# Agrobot_2_0.net
KiCad netlist of a schematic drawn in Altium Designer
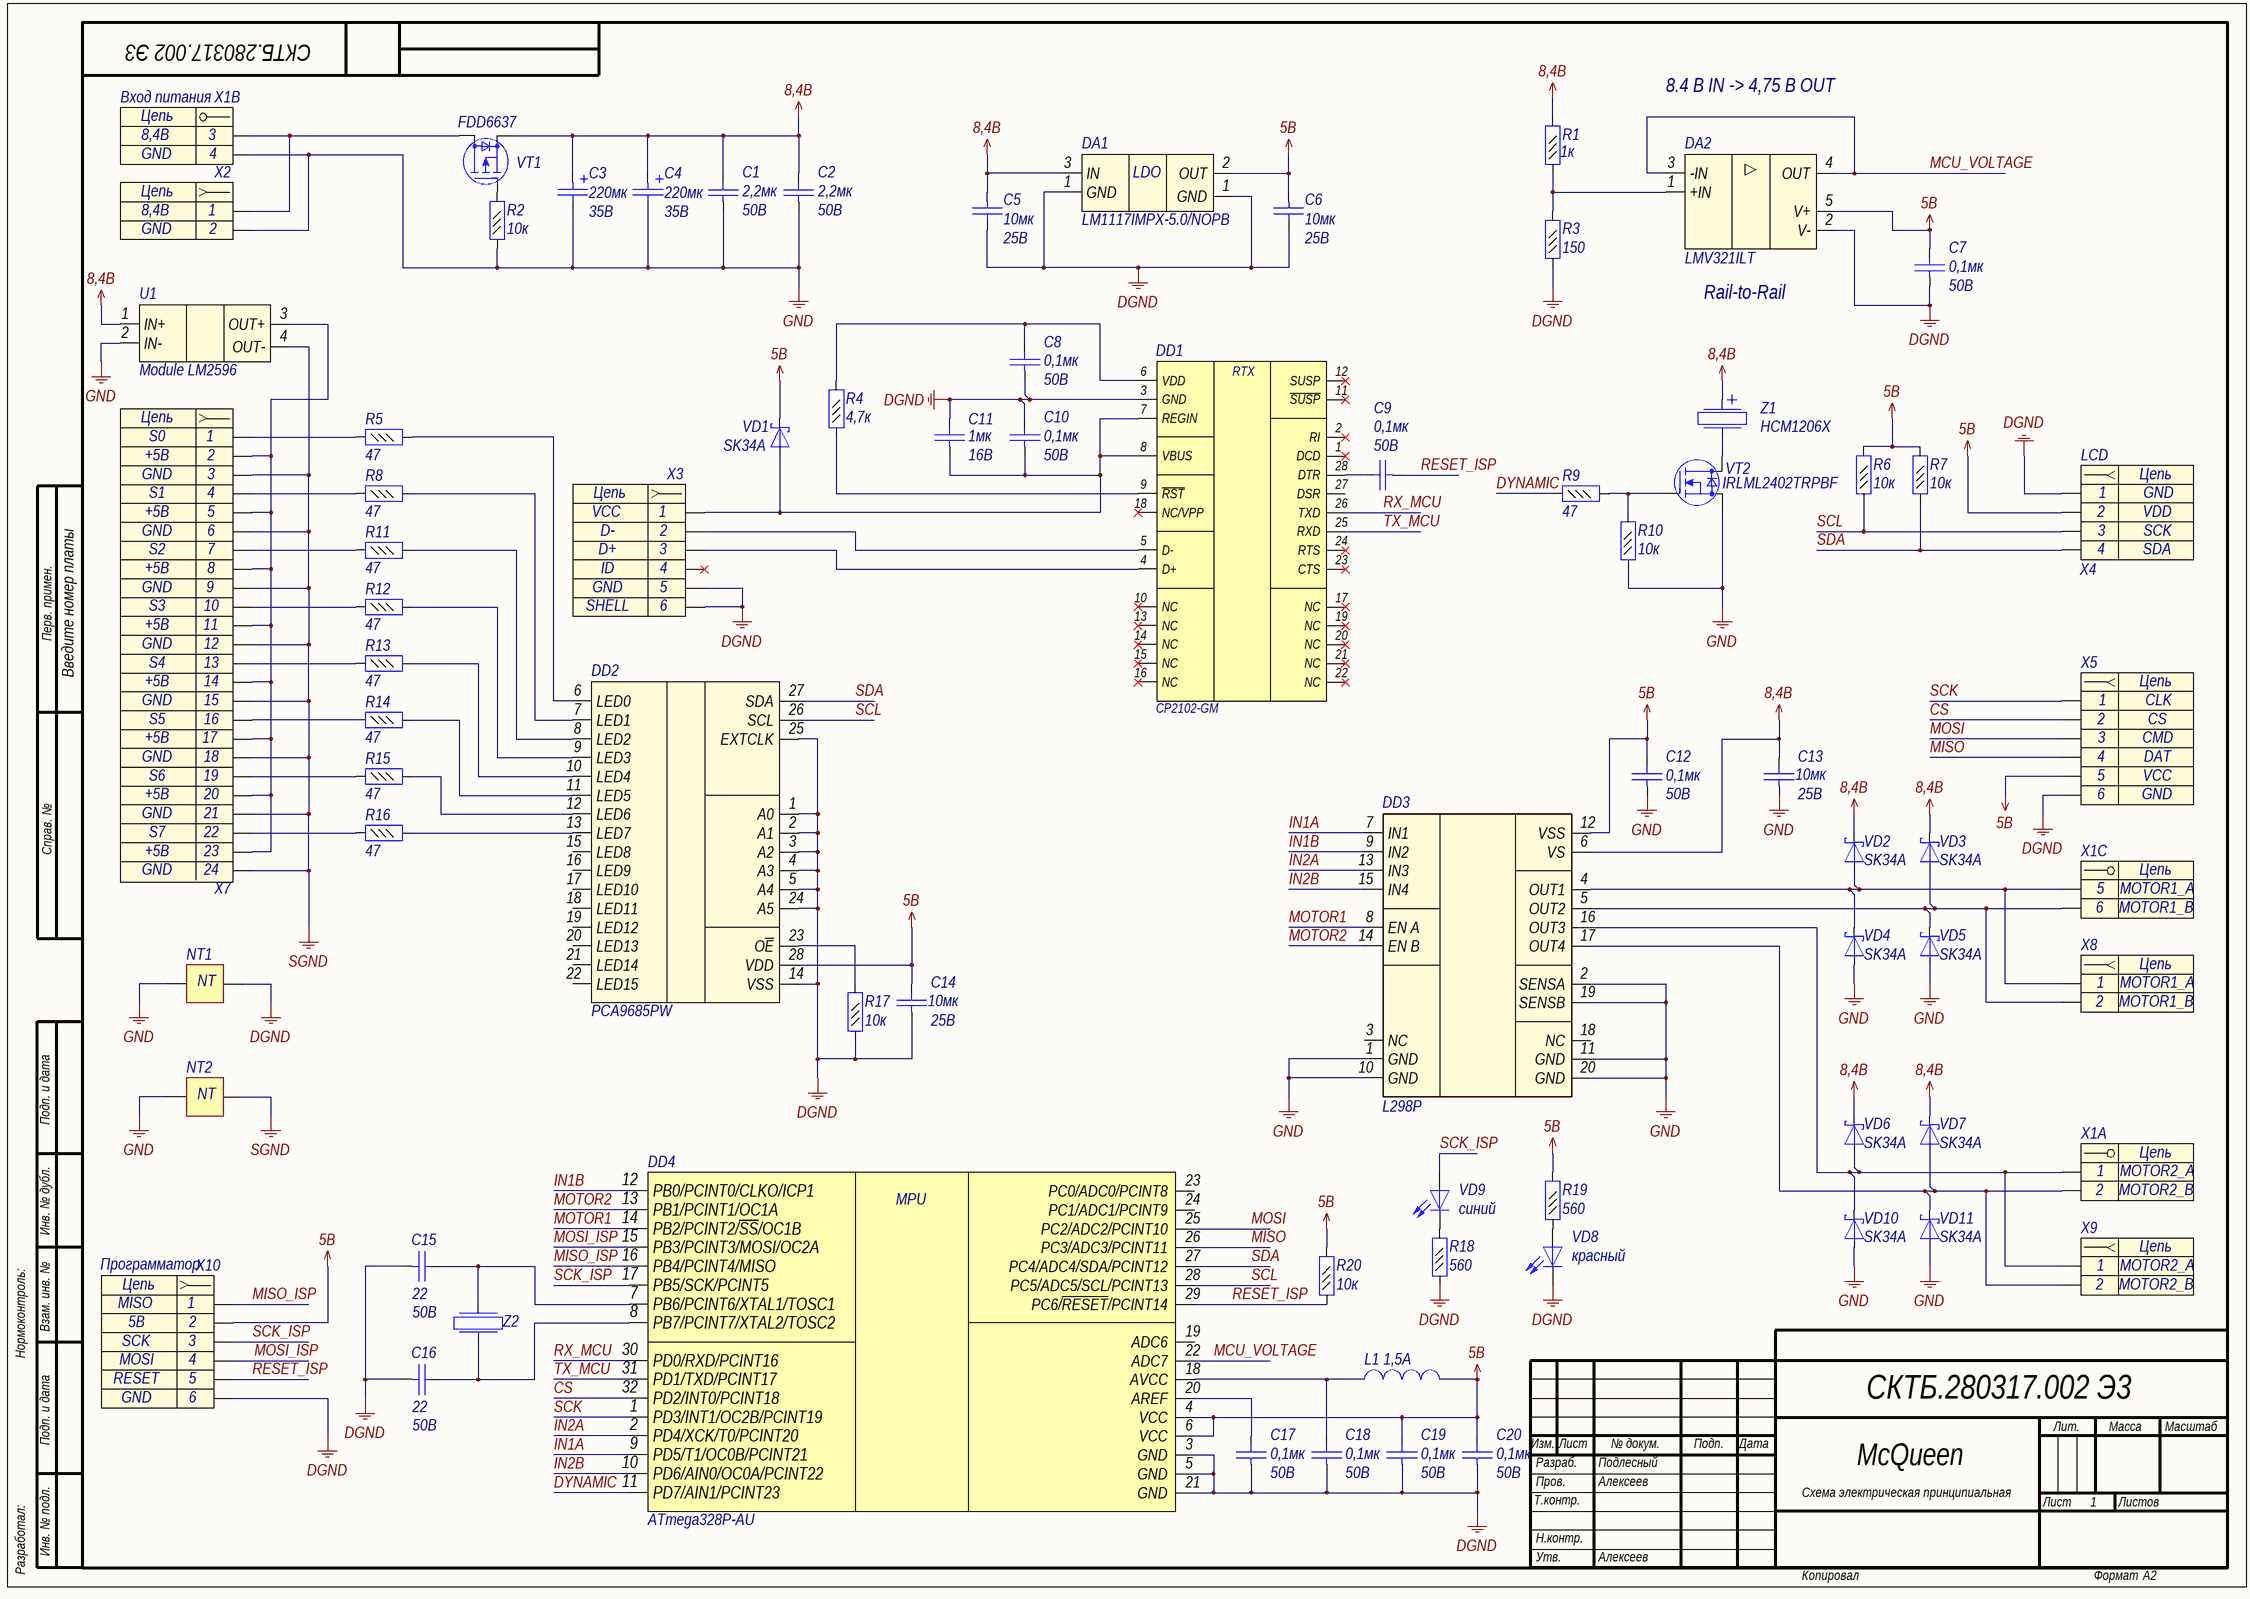
[diagram p0: Agrobot_2.0.SchDoc]

(export (version "E")
  (design (tool "Eeschema 10.0.6"))
  (components
    (comp (ref "C1")
      (value "2,2мк")
      (footprint "C1206")
      (description "Конденсатор")
      (fields
        (field (name "VOLTAGE") "50В")
        (field (name "PART NUMBER") "GRM31CR71H225KA88**L")
        (field (name "Comment") "Capacitor")
      )
      (libsource (lib "MOP44") (part "Capacitor"))
    )
    (comp (ref "C2")
      (value "2,2мк")
      (footprint "C1206")
      (description "Конденсатор")
      (fields
        (field (name "VOLTAGE") "50В")
        (field (name "PART NUMBER") "GRM31CR71H225KA88**L")
        (field (name "Comment") "Capacitor")
      )
      (libsource (lib "MOP44") (part "Capacitor"))
    )
    (comp (ref "C3")
      (value "220мк")
      (footprint "K50-35(8X11.5)_H")
      (description "Конденсатор полярный")
      (fields
        (field (name "VOLTAGE") "35В")
        (field (name "PART NUMBER") "TKR221M1VF11")
        (field (name "Comment") "Capacitor_pol")
      )
      (libsource (lib "MOP44") (part "Capacitor_pol"))
    )
    (comp (ref "C4")
      (value "220мк")
      (footprint "K50-35(8X11.5)_H_MIRROR")
      (description "Конденсатор полярный")
      (fields
        (field (name "VOLTAGE") "35В")
        (field (name "PART NUMBER") "TKR221M1VF11")
        (field (name "Comment") "Capacitor_pol")
      )
      (libsource (lib "MOP44") (part "Capacitor_pol"))
    )
    (comp (ref "C5")
      (value "10мк")
      (footprint "C1210")
      (description "Конденсатор")
      (fields (field (name "VOLTAGE") "25В") (field (name "PART NUMBER") "GRM32ER61A106K"))
      (libsource (lib "MOP44") (part "Capacitor"))
    )
    (comp (ref "C6")
      (value "10мк")
      (footprint "C1210")
      (description "Конденсатор")
      (fields (field (name "VOLTAGE") "25В") (field (name "PART NUMBER") "GRM32ER61A106K"))
      (libsource (lib "MOP44") (part "Capacitor"))
    )
    (comp (ref "C7")
      (value "0,1мк")
      (footprint "C0603")
      (description "Конденсатор")
      (fields (field (name "VOLTAGE") "50B") (field (name "PART NUMBER") "GRM188R71H104KA93D"))
      (libsource (lib "MOP44") (part "Capacitor"))
    )
    (comp (ref "C8")
      (value "0,1мк")
      (footprint "C0603")
      (description "Конденсатор")
      (fields (field (name "VOLTAGE") "50B") (field (name "PART NUMBER") "GRM188R71H104KA93D"))
      (libsource (lib "MOP44") (part "Capacitor"))
    )
    (comp (ref "C9")
      (value "0,1мк")
      (footprint "C0603")
      (description "Конденсатор")
      (fields (field (name "VOLTAGE") "50B") (field (name "PART NUMBER") "GRM188R71H104KA93D"))
      (libsource (lib "MOP44") (part "Capacitor"))
    )
    (comp (ref "C10")
      (value "0,1мк")
      (footprint "C0603")
      (description "Конденсатор")
      (fields (field (name "VOLTAGE") "50B") (field (name "PART NUMBER") "GRM188R71H104KA93D"))
      (libsource (lib "MOP44") (part "Capacitor"))
    )
    (comp (ref "C11")
      (value "1мк")
      (footprint "C0603")
      (description "Конденсатор")
      (fields (field (name "VOLTAGE") "16B") (field (name "PART NUMBER") "GRM188R71C105KA12D**"))
      (libsource (lib "MOP44") (part "Capacitor"))
    )
    (comp (ref "C12")
      (value "0,1мк")
      (footprint "C0603")
      (description "Конденсатор")
      (fields (field (name "VOLTAGE") "50B") (field (name "PART NUMBER") "GRM188R71H104KA93D"))
      (libsource (lib "MOP44") (part "Capacitor"))
    )
    (comp (ref "C13")
      (value "10мк")
      (footprint "C1210")
      (description "Конденсатор")
      (fields
        (field (name "VOLTAGE") "25В")
        (field (name "PART NUMBER") "GRM32ER61A106K")
        (field (name "Comment") "Capacitor")
      )
      (libsource (lib "MOP44") (part "Capacitor"))
    )
    (comp (ref "C14")
      (value "10мк")
      (footprint "C1210")
      (description "Конденсатор")
      (fields
        (field (name "VOLTAGE") "25В")
        (field (name "PART NUMBER") "GRM32ER61A106K")
        (field (name "Comment") "Capacitor")
      )
      (libsource (lib "MOP44") (part "Capacitor"))
    )
    (comp (ref "C15")
      (value "22")
      (footprint "C0603")
      (description "Конденсатор")
      (fields (field (name "VOLTAGE") "50B") (field (name "PART NUMBER") "CC0603JRNPO9BN220"))
      (libsource (lib "MOP44") (part "Capacitor"))
    )
    (comp (ref "C16")
      (value "22")
      (footprint "C0603")
      (description "Конденсатор")
      (fields (field (name "VOLTAGE") "50B") (field (name "PART NUMBER") "CC0603JRNPO9BN220"))
      (libsource (lib "MOP44") (part "Capacitor"))
    )
    (comp (ref "C17")
      (value "0,1мк")
      (footprint "C0603")
      (description "Конденсатор")
      (fields (field (name "VOLTAGE") "50B") (field (name "PART NUMBER") "GRM188R71H104KA93D"))
      (libsource (lib "MOP44") (part "Capacitor"))
    )
    (comp (ref "C18")
      (value "0,1мк")
      (footprint "C0603")
      (description "Конденсатор")
      (fields (field (name "VOLTAGE") "50B") (field (name "PART NUMBER") "GRM188R71H104KA93D"))
      (libsource (lib "MOP44") (part "Capacitor"))
    )
    (comp (ref "C19")
      (value "0,1мк")
      (footprint "C0603")
      (description "Конденсатор")
      (fields (field (name "VOLTAGE") "50B") (field (name "PART NUMBER") "GRM188R71H104KA93D"))
      (libsource (lib "MOP44") (part "Capacitor"))
    )
    (comp (ref "C20")
      (value "0,1мк")
      (footprint "C0603")
      (description "Конденсатор")
      (fields (field (name "VOLTAGE") "50B") (field (name "PART NUMBER") "GRM188R71H104KA93D"))
      (libsource (lib "MOP44") (part "Capacitor"))
    )
    (comp (ref "DA1")
      (value "LM1117IMPX")
      (footprint "SOT-223")
      (description "Low-Dropout Regulator for 5-V to 3.3-V Conversion")
      (fields
        (field (name "PART NUMBER") "LM1117IMPX-5.0/NOPB")
        (field (name "MANUFACTURER") "Texas Instruments")
      )
      (libsource (lib "MOP44") (part "LM1117IMPX"))
    )
    (comp (ref "DA2")
      (value "LMV321ILT")
      (footprint "SOT23-5")
      (description "HIGH-DRIVE OPERATIONAL AMPLIFIERS WITH SHUTDOWN")
      (libsource (lib "MOP44") (part "LMV321ILT"))
    )
    (comp (ref "DD1")
      (value "CP2102-GM")
      (footprint "QFN28")
      (description "USB-UART преобразователь")
      (libsource (lib "MOP44") (part "CP2102-GM"))
    )
    (comp (ref "DD2")
      (value "PCA9685PW")
      (footprint "TSSOP28")
      (description "Драйвер светодиода, 16 выходов")
      (libsource (lib "MOP44") (part "PCA9685PW"))
    )
    (comp (ref "DD3")
      (value "L298P")
      (footprint "POWERSO20")
      (description "FULL BRIDGE DC MOTOR DRIVER")
      (libsource (lib "MOP44") (part "L298P"))
    )
    (comp (ref "DD4")
      (value "ATmega328P-AU")
      (footprint "TQFP-32")
      (description "Микроконтроллер 8-Бит, picoPower, AVR, 20МГц, 32КБ Flash")
      (fields (field (name "PART NUMBER") "ATmega328P-AU"))
      (libsource (lib "MOP44") (part "ATmega328P-AU"))
    )
    (comp (ref "L1")
      (value "Inductor")
      (footprint "L0603")
      (description "EMI Suppression Filter")
      (fields (field (name "RATED CURRENT") "1,5A") (field (name "PART NUMBER") "BLM18PG181SN1D"))
      (libsource (lib "MOP44") (part "Inductor"))
    )
    (comp (ref "NT1")
      (value "Pofigistor")
      (footprint "Pofigistor0603")
      (libsource (lib "MOP44") (part "Pofigistor"))
    )
    (comp (ref "NT2")
      (value "Pofigistor")
      (footprint "Pofigistor0603")
      (libsource (lib "MOP44") (part "Pofigistor"))
    )
    (comp (ref "R1")
      (value "1к")
      (footprint "R0603")
      (description "Резистор")
      (fields (field (name "PART NUMBER") "RC0603FR-071KL") (field (name "POWER") "0,062Вт"))
      (libsource (lib "") (part "Resistor_0,062Вт_1"))
    )
    (comp (ref "R2")
      (value "10к")
      (footprint "R0603")
      (description "Резистор")
      (fields (field (name "PART NUMBER") "RC0603FR-0710KL") (field (name "POWER") "0,062Вт"))
      (libsource (lib "") (part "Resistor_0,062Вт_1"))
    )
    (comp (ref "R3")
      (value "150")
      (footprint "R0603")
      (description "Резистор")
      (fields (field (name "PART NUMBER") "RC0603FR-07150RL") (field (name "POWER") "0,062Вт"))
      (libsource (lib "") (part "Resistor_0,062Вт_1"))
    )
    (comp (ref "R4")
      (value "4,7к")
      (footprint "R0603")
      (description "Резистор")
      (fields (field (name "PART NUMBER") "RC0603FR-074K7") (field (name "POWER") "0,062Вт"))
      (libsource (lib "") (part "Resistor_0,062Вт_1"))
    )
    (comp (ref "R5")
      (value "47")
      (footprint "R0603")
      (description "Резистор")
      (fields (field (name "PART NUMBER") "RC0603FR-0747RL") (field (name "POWER") "0,062Вт"))
      (libsource (lib "MOP44") (part "Resistor_0,062Вт"))
    )
    (comp (ref "R6")
      (value "10к")
      (footprint "R0603")
      (description "Резистор")
      (fields (field (name "PART NUMBER") "RC0603FR-0710KL") (field (name "POWER") "0,062Вт"))
      (libsource (lib "") (part "Resistor_0,062Вт_1"))
    )
    (comp (ref "R7")
      (value "10к")
      (footprint "R0603")
      (description "Резистор")
      (fields (field (name "PART NUMBER") "RC0603FR-0710KL") (field (name "POWER") "0,062Вт"))
      (libsource (lib "") (part "Resistor_0,062Вт_1"))
    )
    (comp (ref "R8")
      (value "47")
      (footprint "R0603")
      (description "Резистор")
      (fields (field (name "PART NUMBER") "RC0603FR-0747RL") (field (name "POWER") "0,062Вт"))
      (libsource (lib "MOP44") (part "Resistor_0,062Вт"))
    )
    (comp (ref "R9")
      (value "47")
      (footprint "R0603")
      (description "Резистор")
      (fields (field (name "PART NUMBER") "RC0603FR-0747RL") (field (name "POWER") "0,062Вт"))
      (libsource (lib "MOP44") (part "Resistor_0,062Вт"))
    )
    (comp (ref "R10")
      (value "10к")
      (footprint "R0603")
      (description "Резистор")
      (fields (field (name "PART NUMBER") "RC0603FR-0710KL") (field (name "POWER") "0,062Вт"))
      (libsource (lib "") (part "Resistor_0,062Вт_1"))
    )
    (comp (ref "R11")
      (value "47")
      (footprint "R0603")
      (description "Резистор")
      (fields (field (name "PART NUMBER") "RC0603FR-0747RL") (field (name "POWER") "0,062Вт"))
      (libsource (lib "MOP44") (part "Resistor_0,062Вт"))
    )
    (comp (ref "R12")
      (value "47")
      (footprint "R0603")
      (description "Резистор")
      (fields (field (name "PART NUMBER") "RC0603FR-0747RL") (field (name "POWER") "0,062Вт"))
      (libsource (lib "MOP44") (part "Resistor_0,062Вт"))
    )
    (comp (ref "R13")
      (value "47")
      (footprint "R0603")
      (description "Резистор")
      (fields (field (name "PART NUMBER") "RC0603FR-0747RL") (field (name "POWER") "0,062Вт"))
      (libsource (lib "MOP44") (part "Resistor_0,062Вт"))
    )
    (comp (ref "R14")
      (value "47")
      (footprint "R0603")
      (description "Резистор")
      (fields (field (name "PART NUMBER") "RC0603FR-0747RL") (field (name "POWER") "0,062Вт"))
      (libsource (lib "MOP44") (part "Resistor_0,062Вт"))
    )
    (comp (ref "R15")
      (value "47")
      (footprint "R0603")
      (description "Резистор")
      (fields (field (name "PART NUMBER") "RC0603FR-0747RL") (field (name "POWER") "0,062Вт"))
      (libsource (lib "MOP44") (part "Resistor_0,062Вт"))
    )
    (comp (ref "R16")
      (value "47")
      (footprint "R0603")
      (description "Резистор")
      (fields (field (name "PART NUMBER") "RC0603FR-0747RL") (field (name "POWER") "0,062Вт"))
      (libsource (lib "MOP44") (part "Resistor_0,062Вт"))
    )
    (comp (ref "R17")
      (value "10к")
      (footprint "R0603")
      (description "Резистор")
      (fields (field (name "PART NUMBER") "RC0603FR-0710KL") (field (name "POWER") "0,062Вт"))
      (libsource (lib "") (part "Resistor_0,062Вт_1"))
    )
    (comp (ref "R18")
      (value "560")
      (footprint "R0603")
      (description "Резистор")
      (fields (field (name "PART NUMBER") "RC0603FR-07560RL") (field (name "POWER") "0,062Вт"))
      (libsource (lib "") (part "Resistor_0,062Вт_1"))
    )
    (comp (ref "R19")
      (value "560")
      (footprint "R0603")
      (description "Резистор")
      (fields (field (name "PART NUMBER") "RC0603FR-07560RL") (field (name "POWER") "0,062Вт"))
      (libsource (lib "") (part "Resistor_0,062Вт_1"))
    )
    (comp (ref "R20")
      (value "10к")
      (footprint "R0603")
      (description "Резистор")
      (fields (field (name "PART NUMBER") "RC0603FR-0710KL") (field (name "POWER") "0,062Вт"))
      (libsource (lib "") (part "Resistor_0,062Вт_1"))
    )
    (comp (ref "U1")
      (value "Module LM2596")
      (footprint "module LM2596")
      (description "Low-Dropout Regulator for 5-V to 3.3-V Conversion")
      (libsource (lib "MOP44") (part "Module LM2596"))
    )
    (comp (ref "VD1")
      (value "DiodeSchottky")
      (footprint "SMA")
      (description "Диод Шоттки")
      (fields (field (name "PART NUMBER") "SK34A"))
      (libsource (lib "MOP44") (part "DiodeSchottky"))
    )
    (comp (ref "VD2")
      (value "DiodeSchottky")
      (footprint "SMA")
      (description "Диод Шоттки")
      (fields (field (name "PART NUMBER") "SK34A"))
      (libsource (lib "MOP44") (part "DiodeSchottky"))
    )
    (comp (ref "VD3")
      (value "DiodeSchottky")
      (footprint "SMA")
      (description "Диод Шоттки")
      (fields (field (name "PART NUMBER") "SK34A"))
      (libsource (lib "MOP44") (part "DiodeSchottky"))
    )
    (comp (ref "VD4")
      (value "DiodeSchottky")
      (footprint "SMA")
      (description "Диод Шоттки")
      (fields (field (name "PART NUMBER") "SK34A"))
      (libsource (lib "MOP44") (part "DiodeSchottky"))
    )
    (comp (ref "VD5")
      (value "DiodeSchottky")
      (footprint "SMA")
      (description "Диод Шоттки")
      (fields (field (name "PART NUMBER") "SK34A"))
      (libsource (lib "MOP44") (part "DiodeSchottky"))
    )
    (comp (ref "VD6")
      (value "DiodeSchottky")
      (footprint "SMA")
      (description "Диод Шоттки")
      (fields (field (name "PART NUMBER") "SK34A"))
      (libsource (lib "MOP44") (part "DiodeSchottky"))
    )
    (comp (ref "VD7")
      (value "DiodeSchottky")
      (footprint "SMA")
      (description "Диод Шоттки")
      (fields (field (name "PART NUMBER") "SK34A"))
      (libsource (lib "MOP44") (part "DiodeSchottky"))
    )
    (comp (ref "VD8")
      (value "красный")
      (footprint "L_0805")
      (description "Светодиод")
      (fields (field (name "PART NUMBER") "KP-2012EC"))
      (libsource (lib "MOP44") (part "LED"))
    )
    (comp (ref "VD9")
      (value "синий")
      (footprint "L_0805")
      (description "Светодиод")
      (fields (field (name "PART NUMBER") "KP-2012MGC"))
      (libsource (lib "MOP44") (part "LED"))
    )
    (comp (ref "VD10")
      (value "DiodeSchottky")
      (footprint "SMA")
      (description "Диод Шоттки")
      (fields (field (name "PART NUMBER") "SK34A"))
      (libsource (lib "MOP44") (part "DiodeSchottky"))
    )
    (comp (ref "VD11")
      (value "DiodeSchottky")
      (footprint "SMA")
      (description "Диод Шоттки")
      (fields (field (name "PART NUMBER") "SK34A"))
      (libsource (lib "MOP44") (part "DiodeSchottky"))
    )
    (comp (ref "VT1")
      (value "P-MOSFET")
      (footprint "DPAK")
      (description "N-MOSFET")
      (fields (field (name "PART NUMBER") "FDD6637") (field (name "MANUFACTURER") "Fairchild Semiconductor"))
      (libsource (lib "MOP44") (part "P-MOSFET"))
    )
    (comp (ref "VT2")
      (value "N-MOSFET")
      (footprint "SOT23-3")
      (fields (field (name "PART NUMBER") "IRLML2402TRPBF"))
      (libsource (lib "MOP44") (part "N-MOSFET"))
    )
    (comp (ref "X1")
      (value "Вход питания")
      (footprint "TERMINAL-6WAY-5MM")
      (description "POWER")
      (libsource (lib "") (part "Header_6_motor_1"))
    )
    (comp (ref "X2")
      (value "Header_2_sct")
      (footprint "2HOLE_2.5")
      (description "Разъем - 2 конт. розетка")
      (libsource (lib "") (part "Header_2_sct_1"))
    )
    (comp (ref "X3")
      (value "Header_6_sct")
      (footprint "USB_MICRO_VERT")
      (description "Разъем - 6 конт. розетка")
      (fields (field (name "PART NUMBER") "MK5P"))
      (libsource (lib "") (part "Header_6_sct_1"))
    )
    (comp (ref "X4")
      (value "LCD")
      (footprint "PLS-4HOLES")
      (description "Разъем - 4 конт. розетка")
      (libsource (lib "MOP44") (part "Header_4_sct"))
    )
    (comp (ref "X5")
      (value "Header_6_sct")
      (footprint "PSP_ANTENNA")
      (description "Разъем - 6 конт. розетка")
      (libsource (lib "MOP44") (part "Header_6_sct"))
    )
    (comp (ref "X7")
      (value "Header_24_sct")
      (footprint "PLS-24-3")
      (description "Разъем - 5 конт. розетка")
      (libsource (lib "MOP44") (part "Header_24_sct"))
    )
    (comp (ref "X8")
      (value "Header_2_sct")
      (footprint "2HOLE_2.5")
      (description "Разъем - 2 конт. розетка")
      (libsource (lib "MOP44") (part "Header_2_sct"))
    )
    (comp (ref "X9")
      (value "Header_2_sct")
      (footprint "2HOLE_2.5")
      (description "Разъем - 2 конт. розетка")
      (libsource (lib "MOP44") (part "Header_2_sct"))
    )
    (comp (ref "X10")
      (value "Программатор")
      (footprint "PLS2-6")
      (description "Разъем - 6 конт. розетка")
      (libsource (lib "") (part "Header_6_sct_1"))
    )
    (comp (ref "Z1")
      (value "~")
      (footprint "Buzzer_gen_12mm")
      (description "Пьезоизлучатель звуковой без генератора")
      (fields (field (name "PART NUMBER") "HCM1206X"))
      (libsource (lib "MOP44") (part "Buzzer"))
    )
    (comp (ref "Z2")
      (value "Crystal")
      (footprint "HC-49SM")
      (description "Кварцевый резонатор")
      (fields (field (name "PART NUMBER") "16.000MHzHC-49SM"))
      (libsource (lib "MOP44") (part "Crystal"))
    )
  )
  (nets
    (net (code "1") (name "/CS") (class "Default")
      (node (ref "DD4") (pin "32") (pinfunction "PD2/INT0/PCINT18_32") (pintype "passive"))
      (node (ref "X5") (pin "2") (pinfunction "2_2") (pintype "passive"))
    )
    (net (code "2") (name "/DYNAMIC") (class "Default")
      (node (ref "DD4") (pin "11") (pinfunction "PD7/AIN1/PCINT23_11") (pintype "passive"))
      (node (ref "R9") (pin "1") (pinfunction "1_1") (pintype "passive"))
    )
    (net (code "3") (name "/IN1A") (class "Default")
      (node (ref "DD3") (pin "7") (pinfunction "IN1_7") (pintype "passive"))
      (node (ref "DD4") (pin "9") (pinfunction "PD5/T1/OC0B/PCINT21_9") (pintype "passive"))
    )
    (net (code "4") (name "/IN1B") (class "Default")
      (node (ref "DD3") (pin "9") (pinfunction "IN2_9") (pintype "passive"))
      (node (ref "DD4") (pin "12") (pinfunction "PB0/PCINT0/CLKO/ICP1_12") (pintype "passive"))
    )
    (net (code "5") (name "/IN2A") (class "Default")
      (node (ref "DD3") (pin "13") (pinfunction "IN3_13") (pintype "passive"))
      (node (ref "DD4") (pin "2") (pinfunction "PD4/XCK/T0/PCINT20_2") (pintype "passive"))
    )
    (net (code "6") (name "/IN2B") (class "Default")
      (node (ref "DD3") (pin "15") (pinfunction "IN4_15") (pintype "passive"))
      (node (ref "DD4") (pin "10") (pinfunction "PD6/AIN0/OC0A/PCINT22_10") (pintype "passive"))
    )
    (net (code "7") (name "/MCU_VOLTAGE") (class "Default")
      (node (ref "DA2") (pin "3") (pinfunction "-IN_3") (pintype "passive"))
      (node (ref "DA2") (pin "4") (pinfunction "OUT_4") (pintype "passive"))
      (node (ref "DD4") (pin "22") (pinfunction "ADC7_22") (pintype "passive"))
    )
    (net (code "8") (name "/MISO") (class "Default")
      (node (ref "DD4") (pin "26") (pinfunction "PC3/ADC3/PCINT11_26") (pintype "passive"))
      (node (ref "X5") (pin "4") (pinfunction "4_4") (pintype "passive"))
    )
    (net (code "9") (name "/MISO_ISP") (class "Default")
      (node (ref "DD4") (pin "16") (pinfunction "PB4/PCINT4/MISO_16") (pintype "passive"))
      (node (ref "X10") (pin "1") (pinfunction "1_1") (pintype "passive"))
    )
    (net (code "10") (name "/MOSI") (class "Default")
      (node (ref "DD4") (pin "25") (pinfunction "PC2/ADC2/PCINT10_25") (pintype "passive"))
      (node (ref "X5") (pin "3") (pinfunction "3_3") (pintype "passive"))
    )
    (net (code "11") (name "/MOSI_ISP") (class "Default")
      (node (ref "DD4") (pin "15") (pinfunction "PB3/PCINT3/MOSI/OC2A_15") (pintype "passive"))
      (node (ref "X10") (pin "4") (pinfunction "4_4") (pintype "passive"))
    )
    (net (code "12") (name "/MOTOR1") (class "Default")
      (node (ref "DD3") (pin "8") (pinfunction "EN_A_8") (pintype "passive"))
      (node (ref "DD4") (pin "14") (pinfunction "PB2/PCINT2/~{SS}/OC1B_14") (pintype "passive"))
    )
    (net (code "13") (name "/MOTOR2") (class "Default")
      (node (ref "DD3") (pin "14") (pinfunction "EN_B_14") (pintype "passive"))
      (node (ref "DD4") (pin "13") (pinfunction "PB1/PCINT1/OC1A_13") (pintype "passive"))
    )
    (net (code "14") (name "/RESET_ISP") (class "Default")
      (node (ref "C9") (pin "1") (pinfunction "1_1") (pintype "passive"))
      (node (ref "DD4") (pin "29") (pinfunction "PC6/~{RESET}/PCINT14_29") (pintype "passive"))
      (node (ref "R20") (pin "1") (pinfunction "1_1") (pintype "passive"))
      (node (ref "X10") (pin "5") (pinfunction "5_5") (pintype "passive"))
    )
    (net (code "15") (name "/RX_MCU") (class "Default")
      (node (ref "DD1") (pin "26") (pinfunction "TXD_26") (pintype "passive"))
      (node (ref "DD4") (pin "30") (pinfunction "PD0/RXD/PCINT16_30") (pintype "passive"))
    )
    (net (code "16") (name "/SCK") (class "Default")
      (node (ref "DD4") (pin "1") (pinfunction "PD3/INT1/OC2B/PCINT19_1") (pintype "passive"))
      (node (ref "X5") (pin "1") (pinfunction "1_1") (pintype "passive"))
    )
    (net (code "17") (name "/SCK_ISP") (class "Default")
      (node (ref "DD4") (pin "17") (pinfunction "PB5/SCK/PCINT5_17") (pintype "passive"))
      (node (ref "VD9") (pin "2") (pinfunction "A_2") (pintype "passive"))
      (node (ref "X10") (pin "3") (pinfunction "3_3") (pintype "passive"))
    )
    (net (code "18") (name "/SCL") (class "Default")
      (node (ref "DD2") (pin "26") (pinfunction "SCL_26") (pintype "power_in"))
      (node (ref "DD4") (pin "28") (pinfunction "PC5/ADC5/SCL/PCINT13_28") (pintype "passive"))
      (node (ref "R6") (pin "1") (pinfunction "1_1") (pintype "passive"))
      (node (ref "X4") (pin "3") (pinfunction "3_3") (pintype "passive"))
    )
    (net (code "19") (name "/SDA") (class "Default")
      (node (ref "DD2") (pin "27") (pinfunction "SDA_27") (pintype "power_in"))
      (node (ref "DD4") (pin "27") (pinfunction "PC4/ADC4/SDA/PCINT12_27") (pintype "passive"))
      (node (ref "R7") (pin "1") (pinfunction "1_1") (pintype "passive"))
      (node (ref "X4") (pin "4") (pinfunction "4_4") (pintype "passive"))
    )
    (net (code "20") (name "/TX_MCU") (class "Default")
      (node (ref "DD1") (pin "25") (pinfunction "RXD_25") (pintype "passive"))
      (node (ref "DD4") (pin "31") (pinfunction "PD1/TXD/PCINT17_31") (pintype "passive"))
    )
    (net (code "21") (name "5В") (class "Default")
      (node (ref "C12") (pin "2") (pinfunction "2_2") (pintype "passive"))
      (node (ref "C14") (pin "2") (pinfunction "2_2") (pintype "passive"))
      (node (ref "C19") (pin "2") (pinfunction "2_2") (pintype "passive"))
      (node (ref "C20") (pin "2") (pinfunction "2_2") (pintype "passive"))
      (node (ref "C6") (pin "1") (pinfunction "1_1") (pintype "passive"))
      (node (ref "C7") (pin "2") (pinfunction "2_2") (pintype "passive"))
      (node (ref "DA1") (pin "2") (pinfunction "OUT_2") (pintype "power_in"))
      (node (ref "DA2") (pin "5") (pinfunction "V+_5") (pintype "passive"))
      (node (ref "DD2") (pin "28") (pinfunction "VDD_28") (pintype "power_in"))
      (node (ref "DD3") (pin "12") (pinfunction "VSS_12") (pintype "passive"))
      (node (ref "DD4") (pin "4") (pinfunction "VCC_4") (pintype "passive"))
      (node (ref "DD4") (pin "6") (pinfunction "VCC_6") (pintype "passive"))
      (node (ref "L1") (pin "2") (pinfunction "2_2") (pintype "passive"))
      (node (ref "R19") (pin "2") (pinfunction "2_2") (pintype "passive"))
      (node (ref "R20") (pin "2") (pinfunction "2_2") (pintype "passive"))
      (node (ref "R6") (pin "2") (pinfunction "2_2") (pintype "passive"))
      (node (ref "R7") (pin "2") (pinfunction "2_2") (pintype "passive"))
      (node (ref "VD1") (pin "1") (pinfunction "K_1") (pintype "passive"))
      (node (ref "X10") (pin "2") (pinfunction "2_2") (pintype "passive"))
      (node (ref "X4") (pin "2") (pinfunction "2_2") (pintype "passive"))
      (node (ref "X5") (pin "5") (pinfunction "5_5") (pintype "passive"))
    )
    (net (code "22") (name "8,4В") (class "Default")
      (node (ref "C1") (pin "2") (pinfunction "2_2") (pintype "passive"))
      (node (ref "C13") (pin "2") (pinfunction "2_2") (pintype "passive"))
      (node (ref "C2") (pin "2") (pinfunction "2_2") (pintype "passive"))
      (node (ref "C3") (pin "1") (pinfunction "1_1") (pintype "passive"))
      (node (ref "C4") (pin "1") (pinfunction "1_1") (pintype "passive"))
      (node (ref "C5") (pin "1") (pinfunction "1_1") (pintype "passive"))
      (node (ref "DA1") (pin "3") (pinfunction "IN_3") (pintype "power_in"))
      (node (ref "DD3") (pin "6") (pinfunction "VS_6") (pintype "passive"))
      (node (ref "R1") (pin "2") (pinfunction "2_2") (pintype "passive"))
      (node (ref "U1") (pin "1") (pinfunction "IN+_1") (pintype "power_in"))
      (node (ref "VD2") (pin "1") (pinfunction "K_1") (pintype "passive"))
      (node (ref "VD3") (pin "1") (pinfunction "K_1") (pintype "passive"))
      (node (ref "VD6") (pin "1") (pinfunction "K_1") (pintype "passive"))
      (node (ref "VD7") (pin "1") (pinfunction "K_1") (pintype "passive"))
      (node (ref "VT1") (pin "3") (pinfunction "S_3") (pintype "passive"))
      (node (ref "Z1") (pin "1") (pinfunction "1_1") (pintype "passive"))
    )
    (net (code "23") (name "DGND") (class "Default")
      (node (ref "C10") (pin "2") (pinfunction "2_2") (pintype "passive"))
      (node (ref "C11") (pin "2") (pinfunction "2_2") (pintype "passive"))
      (node (ref "C14") (pin "1") (pinfunction "1_1") (pintype "passive"))
      (node (ref "C15") (pin "1") (pinfunction "1_1") (pintype "passive"))
      (node (ref "C16") (pin "1") (pinfunction "1_1") (pintype "passive"))
      (node (ref "C17") (pin "1") (pinfunction "1_1") (pintype "passive"))
      (node (ref "C18") (pin "1") (pinfunction "1_1") (pintype "passive"))
      (node (ref "C19") (pin "1") (pinfunction "1_1") (pintype "passive"))
      (node (ref "C20") (pin "1") (pinfunction "1_1") (pintype "passive"))
      (node (ref "C5") (pin "2") (pinfunction "2_2") (pintype "passive"))
      (node (ref "C6") (pin "2") (pinfunction "2_2") (pintype "passive"))
      (node (ref "C7") (pin "1") (pinfunction "1_1") (pintype "passive"))
      (node (ref "C8") (pin "1") (pinfunction "1_1") (pintype "passive"))
      (node (ref "DA1") (pin "1") (pinfunction "GND_1") (pintype "power_in"))
      (node (ref "DA2") (pin "2") (pinfunction "V-_2") (pintype "passive"))
      (node (ref "DD1") (pin "3") (pinfunction "GND_3") (pintype "passive"))
      (node (ref "DD2") (pin "1") (pinfunction "A0_1") (pintype "power_in"))
      (node (ref "DD2") (pin "14") (pinfunction "VSS_14") (pintype "power_in"))
      (node (ref "DD2") (pin "2") (pinfunction "A1_2") (pintype "power_in"))
      (node (ref "DD2") (pin "24") (pinfunction "A5_24") (pintype "power_in"))
      (node (ref "DD2") (pin "25") (pinfunction "EXTCLK_25") (pintype "power_in"))
      (node (ref "DD2") (pin "3") (pinfunction "A2_3") (pintype "power_in"))
      (node (ref "DD2") (pin "4") (pinfunction "A3_4") (pintype "power_in"))
      (node (ref "DD2") (pin "5") (pinfunction "A4_5") (pintype "power_in"))
      (node (ref "DD4") (pin "21") (pinfunction "GND_21") (pintype "passive"))
      (node (ref "DD4") (pin "3") (pinfunction "GND_3") (pintype "passive"))
      (node (ref "DD4") (pin "5") (pinfunction "GND_5") (pintype "passive"))
      (node (ref "NT1") (pin "2") (pinfunction "2_2") (pintype "passive"))
      (node (ref "R17") (pin "1") (pinfunction "1_1") (pintype "passive"))
      (node (ref "R18") (pin "1") (pinfunction "1_1") (pintype "passive"))
      (node (ref "R3") (pin "1") (pinfunction "1_1") (pintype "passive"))
      (node (ref "VD8") (pin "1") (pinfunction "K_1") (pintype "passive"))
      (node (ref "X10") (pin "6") (pinfunction "6_6") (pintype "passive"))
      (node (ref "X3") (pin "5") (pinfunction "5_5") (pintype "passive"))
      (node (ref "X3") (pin "6") (pinfunction "6_6") (pintype "passive"))
      (node (ref "X4") (pin "1") (pinfunction "1_1") (pintype "passive"))
      (node (ref "X5") (pin "6") (pinfunction "6_6") (pintype "passive"))
    )
    (net (code "24") (name "GND") (class "Default")
      (node (ref "C1") (pin "1") (pinfunction "1_1") (pintype "passive"))
      (node (ref "C12") (pin "1") (pinfunction "1_1") (pintype "passive"))
      (node (ref "C13") (pin "1") (pinfunction "1_1") (pintype "passive"))
      (node (ref "C2") (pin "1") (pinfunction "1_1") (pintype "passive"))
      (node (ref "C3") (pin "2") (pinfunction "2_2") (pintype "passive"))
      (node (ref "C4") (pin "2") (pinfunction "2_2") (pintype "passive"))
      (node (ref "DD3") (pin "1") (pinfunction "GND_1") (pintype "passive"))
      (node (ref "DD3") (pin "10") (pinfunction "GND_10") (pintype "passive"))
      (node (ref "DD3") (pin "11") (pinfunction "GND_11") (pintype "passive"))
      (node (ref "DD3") (pin "19") (pinfunction "SENSB_19") (pintype "passive"))
      (node (ref "DD3") (pin "2") (pinfunction "SENSA_2") (pintype "passive"))
      (node (ref "DD3") (pin "20") (pinfunction "GND_20") (pintype "passive"))
      (node (ref "NT1") (pin "1") (pinfunction "1_1") (pintype "passive"))
      (node (ref "NT2") (pin "1") (pinfunction "1_1") (pintype "passive"))
      (node (ref "R10") (pin "1") (pinfunction "1_1") (pintype "passive"))
      (node (ref "R2") (pin "1") (pinfunction "1_1") (pintype "passive"))
      (node (ref "U1") (pin "2") (pinfunction "IN-_2") (pintype "power_in"))
      (node (ref "VD10") (pin "2") (pinfunction "A_2") (pintype "passive"))
      (node (ref "VD11") (pin "2") (pinfunction "A_2") (pintype "passive"))
      (node (ref "VD4") (pin "2") (pinfunction "A_2") (pintype "passive"))
      (node (ref "VD5") (pin "2") (pinfunction "A_2") (pintype "passive"))
      (node (ref "VT2") (pin "2") (pinfunction "S_2") (pintype "passive"))
      (node (ref "X1") (pin "4") (pinfunction "4_4") (pintype "passive"))
      (node (ref "X2") (pin "2") (pinfunction "2_2") (pintype "passive"))
    )
    (net (code "25") (name "Net-(DA2-+IN)") (class "Default")
      (node (ref "DA2") (pin "1") (pinfunction "+IN_1") (pintype "passive"))
      (node (ref "R1") (pin "1") (pinfunction "1_1") (pintype "passive"))
      (node (ref "R3") (pin "2") (pinfunction "2_2") (pintype "passive"))
    )
    (net (code "26") (name "Net-(DD1-D+)") (class "Default")
      (node (ref "DD1") (pin "4") (pinfunction "D+_4") (pintype "passive"))
      (node (ref "X3") (pin "3") (pinfunction "3_3") (pintype "passive"))
    )
    (net (code "27") (name "Net-(DD1-D-)") (class "Default")
      (node (ref "DD1") (pin "5") (pinfunction "D-_5") (pintype "passive"))
      (node (ref "X3") (pin "2") (pinfunction "2_2") (pintype "passive"))
    )
    (net (code "28") (name "Net-(DD1-DTR)") (class "Default")
      (node (ref "C9") (pin "2") (pinfunction "2_2") (pintype "passive"))
      (node (ref "DD1") (pin "28") (pinfunction "DTR_28") (pintype "passive"))
    )
    (net (code "29") (name "Net-(DD1-REGIN)") (class "Default")
      (node (ref "C10") (pin "1") (pinfunction "1_1") (pintype "passive"))
      (node (ref "C11") (pin "1") (pinfunction "1_1") (pintype "passive"))
      (node (ref "DD1") (pin "7") (pinfunction "REGIN_7") (pintype "passive"))
      (node (ref "DD1") (pin "8") (pinfunction "VBUS_8") (pintype "passive"))
      (node (ref "VD1") (pin "2") (pinfunction "A_2") (pintype "passive"))
      (node (ref "X3") (pin "1") (pinfunction "1_1") (pintype "passive"))
    )
    (net (code "30") (name "Net-(DD1-VDD)") (class "Default")
      (node (ref "C8") (pin "2") (pinfunction "2_2") (pintype "passive"))
      (node (ref "DD1") (pin "6") (pinfunction "VDD_6") (pintype "passive"))
      (node (ref "R4") (pin "2") (pinfunction "2_2") (pintype "passive"))
    )
    (net (code "31") (name "Net-(DD1-~{RST})") (class "Default")
      (node (ref "DD1") (pin "9") (pinfunction "~{RST}_9") (pintype "passive"))
      (node (ref "R4") (pin "1") (pinfunction "1_1") (pintype "passive"))
    )
    (net (code "32") (name "Net-(DD2-LED0)") (class "Default")
      (node (ref "DD2") (pin "6") (pinfunction "LED0_6") (pintype "power_in"))
      (node (ref "R5") (pin "2") (pinfunction "2_2") (pintype "passive"))
    )
    (net (code "33") (name "Net-(DD2-LED1)") (class "Default")
      (node (ref "DD2") (pin "7") (pinfunction "LED1_7") (pintype "power_in"))
      (node (ref "R8") (pin "2") (pinfunction "2_2") (pintype "passive"))
    )
    (net (code "34") (name "Net-(DD2-LED2)") (class "Default")
      (node (ref "DD2") (pin "8") (pinfunction "LED2_8") (pintype "power_in"))
      (node (ref "R11") (pin "2") (pinfunction "2_2") (pintype "passive"))
    )
    (net (code "35") (name "Net-(DD2-LED3)") (class "Default")
      (node (ref "DD2") (pin "9") (pinfunction "LED3_9") (pintype "power_in"))
      (node (ref "R12") (pin "2") (pinfunction "2_2") (pintype "passive"))
    )
    (net (code "36") (name "Net-(DD2-LED4)") (class "Default")
      (node (ref "DD2") (pin "10") (pinfunction "LED4_10") (pintype "power_in"))
      (node (ref "R13") (pin "2") (pinfunction "2_2") (pintype "passive"))
    )
    (net (code "37") (name "Net-(DD2-LED5)") (class "Default")
      (node (ref "DD2") (pin "11") (pinfunction "LED5_11") (pintype "power_in"))
      (node (ref "R14") (pin "2") (pinfunction "2_2") (pintype "passive"))
    )
    (net (code "38") (name "Net-(DD2-LED6)") (class "Default")
      (node (ref "DD2") (pin "12") (pinfunction "LED6_12") (pintype "power_in"))
      (node (ref "R15") (pin "2") (pinfunction "2_2") (pintype "passive"))
    )
    (net (code "39") (name "Net-(DD2-LED7)") (class "Default")
      (node (ref "DD2") (pin "13") (pinfunction "LED7_13") (pintype "power_in"))
      (node (ref "R16") (pin "2") (pinfunction "2_2") (pintype "passive"))
    )
    (net (code "40") (name "Net-(DD2-O~{E})") (class "Default")
      (node (ref "DD2") (pin "23") (pinfunction "O~{E}_23") (pintype "power_in"))
      (node (ref "R17") (pin "2") (pinfunction "2_2") (pintype "passive"))
    )
    (net (code "41") (name "Net-(DD3-OUT1)") (class "Default")
      (node (ref "DD3") (pin "4") (pinfunction "OUT1_4") (pintype "passive"))
      (node (ref "VD2") (pin "2") (pinfunction "A_2") (pintype "passive"))
      (node (ref "VD4") (pin "1") (pinfunction "K_1") (pintype "passive"))
      (node (ref "X1") (pin "5") (pinfunction "5_5") (pintype "passive"))
      (node (ref "X8") (pin "1") (pinfunction "1_1") (pintype "passive"))
    )
    (net (code "42") (name "Net-(DD3-OUT2)") (class "Default")
      (node (ref "DD3") (pin "5") (pinfunction "OUT2_5") (pintype "passive"))
      (node (ref "VD3") (pin "2") (pinfunction "A_2") (pintype "passive"))
      (node (ref "VD5") (pin "1") (pinfunction "K_1") (pintype "passive"))
      (node (ref "X1") (pin "6") (pinfunction "6_6") (pintype "passive"))
      (node (ref "X8") (pin "2") (pinfunction "2_2") (pintype "passive"))
    )
    (net (code "43") (name "Net-(DD3-OUT3)") (class "Default")
      (node (ref "DD3") (pin "16") (pinfunction "OUT3_16") (pintype "passive"))
      (node (ref "VD10") (pin "1") (pinfunction "K_1") (pintype "passive"))
      (node (ref "VD6") (pin "2") (pinfunction "A_2") (pintype "passive"))
      (node (ref "X1") (pin "1") (pinfunction "1_1") (pintype "passive"))
      (node (ref "X9") (pin "1") (pinfunction "1_1") (pintype "passive"))
    )
    (net (code "44") (name "Net-(DD3-OUT4)") (class "Default")
      (node (ref "DD3") (pin "17") (pinfunction "OUT4_17") (pintype "passive"))
      (node (ref "VD11") (pin "1") (pinfunction "K_1") (pintype "passive"))
      (node (ref "VD7") (pin "2") (pinfunction "A_2") (pintype "passive"))
      (node (ref "X1") (pin "2") (pinfunction "2_2") (pintype "passive"))
      (node (ref "X9") (pin "2") (pinfunction "2_2") (pintype "passive"))
    )
    (net (code "45") (name "Net-(DD4-AREF)") (class "Default")
      (node (ref "C17") (pin "2") (pinfunction "2_2") (pintype "passive"))
      (node (ref "DD4") (pin "20") (pinfunction "AREF_20") (pintype "passive"))
    )
    (net (code "46") (name "Net-(DD4-AVCC)") (class "Default")
      (node (ref "C18") (pin "2") (pinfunction "2_2") (pintype "passive"))
      (node (ref "DD4") (pin "18") (pinfunction "AVCC_18") (pintype "passive"))
      (node (ref "L1") (pin "1") (pinfunction "1_1") (pintype "passive"))
    )
    (net (code "47") (name "Net-(DD4-PB6{slash}PCINT6{slash}XTAL1{slash}TOSC1)") (class "Default")
      (node (ref "C15") (pin "2") (pinfunction "2_2") (pintype "passive"))
      (node (ref "DD4") (pin "7") (pinfunction "PB6/PCINT6/XTAL1/TOSC1_7") (pintype "passive"))
      (node (ref "Z2") (pin "2") (pinfunction "2_2") (pintype "passive"))
    )
    (net (code "48") (name "Net-(DD4-PB7{slash}PCINT7{slash}XTAL2{slash}TOSC2)") (class "Default")
      (node (ref "C16") (pin "2") (pinfunction "2_2") (pintype "passive"))
      (node (ref "DD4") (pin "8") (pinfunction "PB7/PCINT7/XTAL2/TOSC2_8") (pintype "passive"))
      (node (ref "Z2") (pin "1") (pinfunction "1_1") (pintype "passive"))
    )
    (net (code "49") (name "Net-(R5-Pad1)") (class "Default")
      (node (ref "R5") (pin "1") (pinfunction "1_1") (pintype "passive"))
      (node (ref "X7") (pin "1") (pinfunction "1_1") (pintype "passive"))
    )
    (net (code "50") (name "Net-(R8-Pad1)") (class "Default")
      (node (ref "R8") (pin "1") (pinfunction "1_1") (pintype "passive"))
      (node (ref "X7") (pin "4") (pinfunction "4_4") (pintype "passive"))
    )
    (net (code "51") (name "Net-(R11-Pad1)") (class "Default")
      (node (ref "R11") (pin "1") (pinfunction "1_1") (pintype "passive"))
      (node (ref "X7") (pin "7") (pinfunction "7_7") (pintype "passive"))
    )
    (net (code "52") (name "Net-(R12-Pad1)") (class "Default")
      (node (ref "R12") (pin "1") (pinfunction "1_1") (pintype "passive"))
      (node (ref "X7") (pin "10") (pinfunction "10_10") (pintype "passive"))
    )
    (net (code "53") (name "Net-(R13-Pad1)") (class "Default")
      (node (ref "R13") (pin "1") (pinfunction "1_1") (pintype "passive"))
      (node (ref "X7") (pin "13") (pinfunction "13_13") (pintype "passive"))
    )
    (net (code "54") (name "Net-(R14-Pad1)") (class "Default")
      (node (ref "R14") (pin "1") (pinfunction "1_1") (pintype "passive"))
      (node (ref "X7") (pin "16") (pinfunction "16_16") (pintype "passive"))
    )
    (net (code "55") (name "Net-(R15-Pad1)") (class "Default")
      (node (ref "R15") (pin "1") (pinfunction "1_1") (pintype "passive"))
      (node (ref "X7") (pin "19") (pinfunction "19_19") (pintype "passive"))
    )
    (net (code "56") (name "Net-(R16-Pad1)") (class "Default")
      (node (ref "R16") (pin "1") (pinfunction "1_1") (pintype "passive"))
      (node (ref "X7") (pin "22") (pinfunction "22_22") (pintype "passive"))
    )
    (net (code "57") (name "Net-(U1-OUT+)") (class "Default")
      (node (ref "U1") (pin "3") (pinfunction "OUT+_3") (pintype "power_in"))
      (node (ref "X7") (pin "11") (pinfunction "11_11") (pintype "passive"))
      (node (ref "X7") (pin "14") (pinfunction "14_14") (pintype "passive"))
      (node (ref "X7") (pin "17") (pinfunction "17_17") (pintype "passive"))
      (node (ref "X7") (pin "2") (pinfunction "2_2") (pintype "passive"))
      (node (ref "X7") (pin "20") (pinfunction "20_20") (pintype "passive"))
      (node (ref "X7") (pin "23") (pinfunction "23_23") (pintype "passive"))
      (node (ref "X7") (pin "5") (pinfunction "5_5") (pintype "passive"))
      (node (ref "X7") (pin "8") (pinfunction "8_8") (pintype "passive"))
    )
    (net (code "58") (name "Net-(VD8-A)") (class "Default")
      (node (ref "R19") (pin "1") (pinfunction "1_1") (pintype "passive"))
      (node (ref "VD8") (pin "2") (pinfunction "A_2") (pintype "passive"))
    )
    (net (code "59") (name "Net-(VD9-K)") (class "Default")
      (node (ref "R18") (pin "2") (pinfunction "2_2") (pintype "passive"))
      (node (ref "VD9") (pin "1") (pinfunction "K_1") (pintype "passive"))
    )
    (net (code "60") (name "Net-(VT1-D)") (class "Default")
      (node (ref "VT1") (pin "2") (pinfunction "D_2") (pintype "passive"))
      (node (ref "X1") (pin "3") (pinfunction "3_3") (pintype "passive"))
      (node (ref "X2") (pin "1") (pinfunction "1_1") (pintype "passive"))
    )
    (net (code "61") (name "Net-(VT1-G)") (class "Default")
      (node (ref "R2") (pin "2") (pinfunction "2_2") (pintype "passive"))
      (node (ref "VT1") (pin "1") (pinfunction "G_1") (pintype "passive"))
    )
    (net (code "62") (name "Net-(VT2-D)") (class "Default")
      (node (ref "VT2") (pin "3") (pinfunction "D_3") (pintype "passive"))
      (node (ref "Z1") (pin "2") (pinfunction "2_2") (pintype "passive"))
    )
    (net (code "63") (name "Net-(VT2-G)") (class "Default")
      (node (ref "R10") (pin "2") (pinfunction "2_2") (pintype "passive"))
      (node (ref "R9") (pin "2") (pinfunction "2_2") (pintype "passive"))
      (node (ref "VT2") (pin "1") (pinfunction "G_1") (pintype "passive"))
    )
    (net (code "64") (name "SGND") (class "Default")
      (node (ref "NT2") (pin "2") (pinfunction "2_2") (pintype "passive"))
      (node (ref "U1") (pin "4") (pinfunction "OUT-_4") (pintype "power_in"))
      (node (ref "X7") (pin "12") (pinfunction "12_12") (pintype "passive"))
      (node (ref "X7") (pin "15") (pinfunction "15_15") (pintype "passive"))
      (node (ref "X7") (pin "18") (pinfunction "18_18") (pintype "passive"))
      (node (ref "X7") (pin "21") (pinfunction "21_21") (pintype "passive"))
      (node (ref "X7") (pin "24") (pinfunction "24_24") (pintype "passive"))
      (node (ref "X7") (pin "3") (pinfunction "3_3") (pintype "passive"))
      (node (ref "X7") (pin "6") (pinfunction "6_6") (pintype "passive"))
      (node (ref "X7") (pin "9") (pinfunction "9_9") (pintype "passive"))
    )
    (net (code "65") (name "unconnected-(DD1-CTS-Pad23)") (class "Default")
      (node (ref "DD1") (pin "23") (pinfunction "CTS_23") (pintype "passive+no_connect"))
    )
    (net (code "66") (name "unconnected-(DD1-DCD-Pad1)") (class "Default")
      (node (ref "DD1") (pin "1") (pinfunction "DCD_1") (pintype "passive+no_connect"))
    )
    (net (code "67") (name "unconnected-(DD1-DSR-Pad27)") (class "Default")
      (node (ref "DD1") (pin "27") (pinfunction "DSR_27") (pintype "passive"))
    )
    (net (code "68") (name "unconnected-(DD1-NC-Pad10)") (class "Default")
      (node (ref "DD1") (pin "10") (pinfunction "NC_10") (pintype "passive+no_connect"))
    )
    (net (code "69") (name "unconnected-(DD1-NC-Pad13)") (class "Default")
      (node (ref "DD1") (pin "13") (pinfunction "NC_13") (pintype "passive+no_connect"))
    )
    (net (code "70") (name "unconnected-(DD1-NC-Pad14)") (class "Default")
      (node (ref "DD1") (pin "14") (pinfunction "NC_14") (pintype "passive+no_connect"))
    )
    (net (code "71") (name "unconnected-(DD1-NC-Pad15)") (class "Default")
      (node (ref "DD1") (pin "15") (pinfunction "NC_15") (pintype "passive+no_connect"))
    )
    (net (code "72") (name "unconnected-(DD1-NC-Pad16)") (class "Default")
      (node (ref "DD1") (pin "16") (pinfunction "NC_16") (pintype "passive+no_connect"))
    )
    (net (code "73") (name "unconnected-(DD1-NC-Pad17)") (class "Default")
      (node (ref "DD1") (pin "17") (pinfunction "NC_17") (pintype "passive+no_connect"))
    )
    (net (code "74") (name "unconnected-(DD1-NC-Pad19)") (class "Default")
      (node (ref "DD1") (pin "19") (pinfunction "NC_19") (pintype "passive+no_connect"))
    )
    (net (code "75") (name "unconnected-(DD1-NC-Pad20)") (class "Default")
      (node (ref "DD1") (pin "20") (pinfunction "NC_20") (pintype "passive+no_connect"))
    )
    (net (code "76") (name "unconnected-(DD1-NC-Pad21)") (class "Default")
      (node (ref "DD1") (pin "21") (pinfunction "NC_21") (pintype "passive+no_connect"))
    )
    (net (code "77") (name "unconnected-(DD1-NC-Pad22)") (class "Default")
      (node (ref "DD1") (pin "22") (pinfunction "NC_22") (pintype "passive+no_connect"))
    )
    (net (code "78") (name "unconnected-(DD1-NC{slash}VPP-Pad18)") (class "Default")
      (node (ref "DD1") (pin "18") (pinfunction "NC/VPP_18") (pintype "passive+no_connect"))
    )
    (net (code "79") (name "unconnected-(DD1-RI-Pad2)") (class "Default")
      (node (ref "DD1") (pin "2") (pinfunction "RI_2") (pintype "passive+no_connect"))
    )
    (net (code "80") (name "unconnected-(DD1-RTS-Pad24)") (class "Default")
      (node (ref "DD1") (pin "24") (pinfunction "RTS_24") (pintype "passive+no_connect"))
    )
    (net (code "81") (name "unconnected-(DD1-SUSP-Pad12)") (class "Default")
      (node (ref "DD1") (pin "12") (pinfunction "SUSP_12") (pintype "passive+no_connect"))
    )
    (net (code "82") (name "unconnected-(DD1-~{SUSP}-Pad11)") (class "Default")
      (node (ref "DD1") (pin "11") (pinfunction "~{SUSP}_11") (pintype "passive+no_connect"))
    )
    (net (code "83") (name "unconnected-(DD2-LED8-Pad15)") (class "Default")
      (node (ref "DD2") (pin "15") (pinfunction "LED8_15") (pintype "power_in"))
    )
    (net (code "84") (name "unconnected-(DD2-LED9-Pad16)") (class "Default")
      (node (ref "DD2") (pin "16") (pinfunction "LED9_16") (pintype "power_in"))
    )
    (net (code "85") (name "unconnected-(DD2-LED10-Pad17)") (class "Default")
      (node (ref "DD2") (pin "17") (pinfunction "LED10_17") (pintype "power_in"))
    )
    (net (code "86") (name "unconnected-(DD2-LED11-Pad18)") (class "Default")
      (node (ref "DD2") (pin "18") (pinfunction "LED11_18") (pintype "power_in"))
    )
    (net (code "87") (name "unconnected-(DD2-LED12-Pad19)") (class "Default")
      (node (ref "DD2") (pin "19") (pinfunction "LED12_19") (pintype "power_in"))
    )
    (net (code "88") (name "unconnected-(DD2-LED13-Pad20)") (class "Default")
      (node (ref "DD2") (pin "20") (pinfunction "LED13_20") (pintype "power_in"))
    )
    (net (code "89") (name "unconnected-(DD2-LED14-Pad21)") (class "Default")
      (node (ref "DD2") (pin "21") (pinfunction "LED14_21") (pintype "power_in"))
    )
    (net (code "90") (name "unconnected-(DD2-LED15-Pad22)") (class "Default")
      (node (ref "DD2") (pin "22") (pinfunction "LED15_22") (pintype "power_in"))
    )
    (net (code "91") (name "unconnected-(DD3-NC-Pad3)") (class "Default")
      (node (ref "DD3") (pin "3") (pinfunction "NC_3") (pintype "passive"))
    )
    (net (code "92") (name "unconnected-(DD3-NC-Pad18)") (class "Default")
      (node (ref "DD3") (pin "18") (pinfunction "NC_18") (pintype "passive"))
    )
    (net (code "93") (name "unconnected-(DD4-ADC6-Pad19)") (class "Default")
      (node (ref "DD4") (pin "19") (pinfunction "ADC6_19") (pintype "passive"))
    )
    (net (code "94") (name "unconnected-(DD4-PC0{slash}ADC0{slash}PCINT8-Pad23)") (class "Default")
      (node (ref "DD4") (pin "23") (pinfunction "PC0/ADC0/PCINT8_23") (pintype "passive"))
    )
    (net (code "95") (name "unconnected-(DD4-PC1{slash}ADC1{slash}PCINT9-Pad24)") (class "Default")
      (node (ref "DD4") (pin "24") (pinfunction "PC1/ADC1/PCINT9_24") (pintype "passive"))
    )
    (net (code "96") (name "unconnected-(X3-Pad4)") (class "Default")
      (node (ref "X3") (pin "4") (pinfunction "4_4") (pintype "passive+no_connect"))
    )
  )
)
